# Power-Sheet-1.net
KiCad netlist of a schematic drawn in Altium Designer
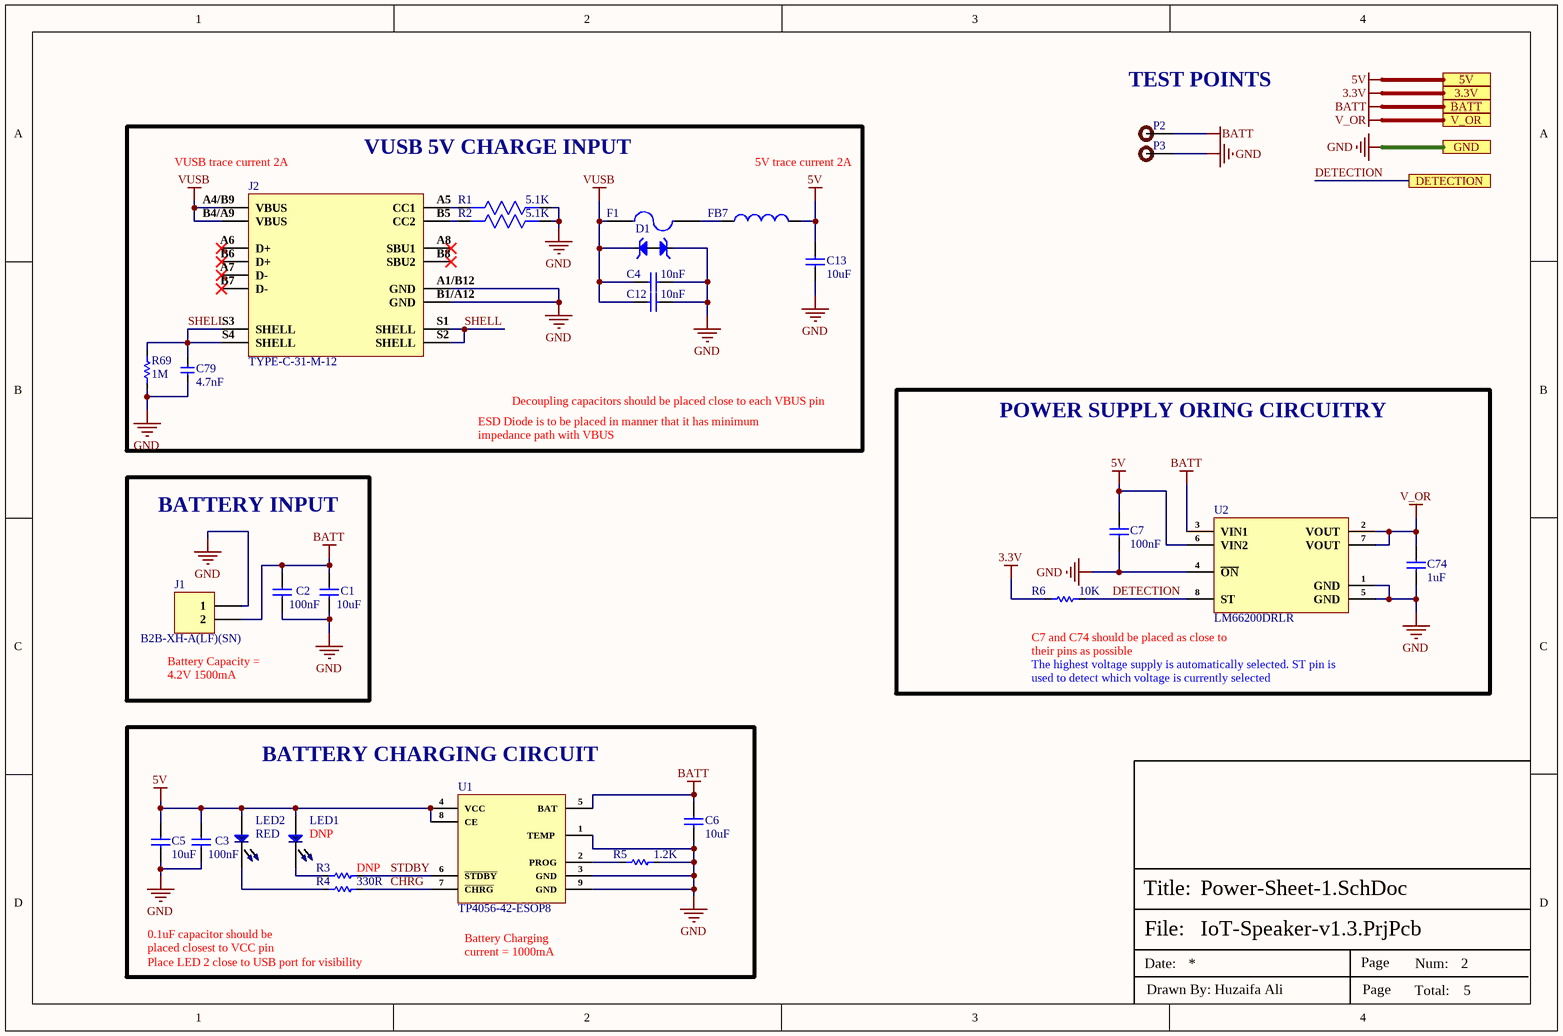
[diagram p0: Power-Sheet-1.SchDoc]

(export (version "E")
  (design (tool "Eeschema 10.0.6"))
  (components
    (comp (ref "C1")
      (value "10uF")
      (footprint "Cap-0805")
      (description "CAP CER 10UF 25V X5R 0805")
      (fields
        (field (name "MANUFACTURER") "Yageo")
        (field (name "MANUFACTURER PART NUMBER") "CC0805KKX5R8BB106")
      )
      (libsource (lib "eSpark_centralized_Library(2022)") (part "CC0805KKX5R8BB106"))
    )
    (comp (ref "C2")
      (value "100nF")
      (footprint "Cap-0402")
      (description "CAP CER 0.1UF 25V X5R 0402")
      (fields
        (field (name "MANUFACTURER") "Yageo")
        (field (name "MANUFACTURER PART NUMBER") "CC0402KRX5R8BB104")
      )
      (libsource (lib "eSpark_centralized_Library(2022)") (part "CC0402KRX5R8BB104"))
    )
    (comp (ref "C3")
      (value "100nF")
      (footprint "Cap-0402")
      (description "CAP CER 0.1UF 25V X5R 0402")
      (fields
        (field (name "MANUFACTURER") "Yageo")
        (field (name "MANUFACTURER PART NUMBER") "CC0402KRX5R8BB104")
      )
      (libsource (lib "eSpark_centralized_Library(2022)") (part "CC0402KRX5R8BB104"))
    )
    (comp (ref "C4")
      (value "10nF")
      (footprint "Cap-0603")
      (description "CAP CER 10000PF 50V C0G/NPO 0603")
      (fields
        (field (name "MANUFACTURER") "Yageo")
        (field (name "MANUFACTURER PART NUMBER") "CC0603JRNPO9BN103")
      )
      (libsource (lib "eSpark_centralized_Library(2022)") (part "CC0603JRNPO9BN103"))
    )
    (comp (ref "C5")
      (value "10uF")
      (footprint "Cap-0805")
      (description "CAP CER 10UF 25V X5R 0805")
      (fields
        (field (name "MANUFACTURER") "Yageo")
        (field (name "MANUFACTURER PART NUMBER") "CC0805KKX5R8BB106")
      )
      (libsource (lib "eSpark_centralized_Library(2022)") (part "CC0805KKX5R8BB106"))
    )
    (comp (ref "C6")
      (value "10uF")
      (footprint "Cap-0805")
      (description "CAP CER 10UF 25V X5R 0805")
      (fields
        (field (name "MANUFACTURER") "Yageo")
        (field (name "MANUFACTURER PART NUMBER") "CC0805KKX5R8BB106")
      )
      (libsource (lib "eSpark_centralized_Library(2022)") (part "CC0805KKX5R8BB106"))
    )
    (comp (ref "C7")
      (value "100nF")
      (footprint "Cap-0402")
      (description "CAP CER 0.1UF 25V X5R 0402")
      (fields
        (field (name "MANUFACTURER") "Yageo")
        (field (name "MANUFACTURER PART NUMBER") "CC0402KRX5R8BB104")
      )
      (libsource (lib "eSpark_centralized_Library(2022)") (part "CC0402KRX5R8BB104"))
    )
    (comp (ref "C12")
      (value "10nF")
      (footprint "Cap-0603")
      (description "CAP CER 10000PF 50V C0G/NPO 0603")
      (fields
        (field (name "MANUFACTURER") "Yageo")
        (field (name "MANUFACTURER PART NUMBER") "CC0603JRNPO9BN103")
      )
      (libsource (lib "eSpark_centralized_Library(2022)") (part "CC0603JRNPO9BN103"))
    )
    (comp (ref "C13")
      (value "10uF")
      (footprint "Cap-0805")
      (description "CAP CER 10UF 25V X5R 0805")
      (fields
        (field (name "MANUFACTURER") "Yageo")
        (field (name "MANUFACTURER PART NUMBER") "CC0805KKX5R8BB106")
      )
      (libsource (lib "eSpark_centralized_Library(2022)") (part "CC0805KKX5R8BB106"))
    )
    (comp (ref "C74")
      (value "1uF")
      (footprint "Cap-0603")
      (description "CAP CER 1UF 25V X5R 0603")
      (fields
        (field (name "MANUFACTURER") "Yageo")
        (field (name "MANUFACTURER PART NUMBER") "CC0603KRX5R8BB105")
      )
      (libsource (lib "eSpark_centralized_Library(2022)") (part "CC0603KRX5R8BB105"))
    )
    (comp (ref "C79")
      (value "4.7nF")
      (footprint "Cap-1206")
      (description "CAP CER 4700PF 1KV X7R 1206")
      (fields
        (field (name "MANUFACTURER") "Yageo")
        (field (name "MANUFACTURER PART NUMBER") "CC1206KKX7RCBB472")
      )
      (libsource (lib "eSpark Libraries") (part "CC1206KKX7RCBB472"))
    )
    (comp (ref "D1")
      (value "PESD5V0H1BSFYL")
      (footprint "DSN0603-2")
      (description "TVS DIODE 5VWM 6.3VC DSN0603-2")
      (fields (field (name "MANUFACTURER") "Nexperia") (field (name "LCSC PART NUMBER") "C477989"))
      (libsource (lib "eSpark Libraries") (part "PESD5V0H1BSFYL"))
    )
    (comp (ref "F1")
      (value "BSMD0805L-200")
      (footprint "Fuse-0805")
      (description "6V 2A 50A 1W -40℃~+85℃ 4A 4mΩ 5s 45mΩ 0805 Resettable Fuses ROHS")
      (fields (field (name "MANUFACTURER") "BHFUSE") (field (name "LCSC PART NUMBER") "C2757931"))
      (libsource (lib "eSpark_centralized_Library(2022)") (part "BSMD0805L-200"))
    )
    (comp (ref "FB7")
      (value "100MHz")
      (footprint "IND-1206")
      (description "FERRITE BEAD 120 OHM 1206 1LN")
      (fields
        (field (name "MANUFACTURER") "Murata")
        (field (name "MANUFACTURER PART NUMBER") "BLM31PG121SN1L")
      )
      (libsource (lib "eSpark_centralized_Library(2022)") (part "BLM31PG121SN1L"))
    )
    (comp (ref "J1")
      (value "B2B-XH-A(LF)(SN)")
      (footprint "B2B-XH-A(LF)(SN)_")
      (description "Conn Shrouded Header (4 Sides) HDR 2 POS 2.5mm Solder ST Thru-Hole Box")
      (fields (field (name "MANUFACTURER") "JST") (field (name "LCSC PART NUMBER") "C158012"))
      (libsource (lib "eSpark_centralized_Library(2022)") (part "B2B-XH-A(LF)(SN)"))
    )
    (comp (ref "J2")
      (value "TYPE-C-31-M-12")
      (footprint "TYPE-C-31-M-12_")
      (description "250mA 1 16 Female Type-C SMD USB Connectors ROHS")
      (fields
        (field (name "MANUFACTURER") "Korean Hroparts Elec")
        (field (name "LCSC PART NUMBER") "C165948")
      )
      (libsource (lib "eSpark_centralized_Library(2022)") (part "TYPE-C-31-M-12"))
    )
    (comp (ref "LED1")
      (value "DNP")
      (footprint "LED-0603")
      (description "Emerald 0603 Light Emitting Diodes (LED) ROHS")
      (fields
        (field (name "MANUFACTURER") "Foshan NationStar Optoelectronics")
        (field (name "MANUFACTURER PART NUMBER") "NCD0603G2")
      )
      (libsource (lib "eSpark_centralized_Library(2022)") (part "NCD0603G2"))
    )
    (comp (ref "LED2")
      (value "RED")
      (footprint "LED-0603")
      (description "0603 Light Emitting Diodes (LED) ROHS")
      (fields
        (field (name "MANUFACTURER") "Foshan NationStar Optoelectronics")
        (field (name "MANUFACTURER PART NUMBER") "NCD0603R3")
      )
      (libsource (lib "eSpark_centralized_Library(2022)") (part "NCD0603R3"))
    )
    (comp (ref "P2")
      (value "TEST POINT")
      (footprint "Test-point")
      (description "Test Point ON")
      (libsource (lib "eSpark_centralized_Library(2022)") (part "TEST POINT"))
    )
    (comp (ref "P3")
      (value "TEST POINT")
      (footprint "Test-point")
      (description "Test Point ON")
      (libsource (lib "eSpark_centralized_Library(2022)") (part "TEST POINT"))
    )
    (comp (ref "R1")
      (value "5.1K")
      (footprint "Res-0603")
      (description "RES 5.1K OHM 1% 1/10W 0603")
      (fields
        (field (name "MANUFACTURER") "Yageo")
        (field (name "MANUFACTURER PART NUMBER") "RC0603FR-075K1L")
      )
      (libsource (lib "eSpark_centralized_Library(2022)") (part "RC0603FR-075K1L"))
    )
    (comp (ref "R2")
      (value "5.1K")
      (footprint "Res-0603")
      (description "RES 5.1K OHM 1% 1/10W 0603")
      (fields
        (field (name "MANUFACTURER") "Yageo")
        (field (name "MANUFACTURER PART NUMBER") "RC0603FR-075K1L")
      )
      (libsource (lib "eSpark_centralized_Library(2022)") (part "RC0603FR-075K1L"))
    )
    (comp (ref "R3")
      (value "DNP")
      (footprint "Res-0603")
      (description "RES SMD 220 OHM 1% 1/10W 0603")
      (fields
        (field (name "MANUFACTURER") "Yageo")
        (field (name "MANUFACTURER PART NUMBER") "RC0603FR-07220RL")
      )
      (libsource (lib "eSpark_centralized_Library(2022)") (part "RC0603FR-07220RL"))
    )
    (comp (ref "R4")
      (value "330R")
      (footprint "Res-0603")
      (description "RES  SMD 330R 100 mW 0603")
      (fields
        (field (name "MANUFACTURER") "Yageo")
        (field (name "MANUFACTURER PART NUMBER") "RC0603JR-07330RL")
      )
      (libsource (lib "eSpark_centralized_Library(2022)") (part "RC0603JR-07330RL"))
    )
    (comp (ref "R5")
      (value "1.2K")
      (footprint "Res-0603")
      (description "Thick Film Resistors 75V 1.2kΩ 0603 Chip Resistor - Surface Mount ROHS")
      (fields
        (field (name "MANUFACTURER") "UNI-ROYAL")
        (field (name "MANUFACTURER PART NUMBER") "0603WAF1201T5E")
      )
      (libsource (lib "eSpark_centralized_Library(2022)") (part "0603WAF1201T5E"))
    )
    (comp (ref "R6")
      (value "10K")
      (footprint "Res-0603")
      (description "RES SMD 10K Ohm 1% 1/10W 0603")
      (fields
        (field (name "MANUFACTURER") "Yageo")
        (field (name "MANUFACTURER PART NUMBER") "RC0603FR-0710KL")
      )
      (libsource (lib "eSpark_centralized_Library(2022)") (part "RC0603FR-0710KL"))
    )
    (comp (ref "R69")
      (value "1M")
      (footprint "Res-0603")
      (description "RES SMD 1M OHM 1% 1/10W 0603")
      (fields
        (field (name "MANUFACTURER") "Yageo")
        (field (name "MANUFACTURER PART NUMBER") "RC0603FR-071ML")
      )
      (libsource (lib "eSpark Libraries") (part "RC0603FR-071ML"))
    )
    (comp (ref "U1")
      (value "TP4056-42-ESOP8")
      (footprint "ESOP-8")
      (description "ESOP-8 Battery Management ICs ROHS")
      (fields (field (name "MANUFACTURER") "TOPPOWER") (field (name "LCSC PART NUMBER") "C16581"))
      (libsource (lib "eSpark_centralized_Library(2022)") (part "TP4056-42-ESOP8"))
    )
    (comp (ref "U2")
      (value "LM66200DRLR")
      (footprint "SOT-583")
      (description "OR Controller N+1 ORing Controller N-Channel 2:1 SOT-583")
      (fields (field (name "MANUFACTURER") "Texas Instruments") (field (name "LCSC PART NUMBER") "C3235556"))
      (libsource (lib "eSpark_centralized_Library(2022)") (part "LM66200DRLR"))
    )
  )
  (nets
    (net (code "1") (name "/CHRG") (class "Default")
      (node (ref "R4") (pin "2") (pinfunction "2_2") (pintype "passive"))
      (node (ref "U1") (pin "7") (pinfunction "~{CHRG}_7") (pintype "passive"))
    )
    (net (code "2") (name "/DETECTION") (class "Default")
      (node (ref "R6") (pin "2") (pinfunction "2_2") (pintype "passive"))
      (node (ref "U2") (pin "8") (pinfunction "ST_8") (pintype "passive"))
    )
    (net (code "3") (name "/SHELL") (class "Default")
      (node (ref "C79") (pin "2") (pinfunction "2_2") (pintype "passive"))
      (node (ref "J2") (pin "S1") (pinfunction "SHELL_S1") (pintype "passive"))
      (node (ref "J2") (pin "S2") (pinfunction "SHELL_S2") (pintype "passive"))
      (node (ref "J2") (pin "S3") (pinfunction "SHELL_S3") (pintype "passive"))
      (node (ref "J2") (pin "S4") (pinfunction "SHELL_S4") (pintype "passive"))
      (node (ref "R69") (pin "2") (pinfunction "2_2") (pintype "passive"))
    )
    (net (code "4") (name "/STDBY") (class "Default")
      (node (ref "R3") (pin "2") (pinfunction "2_2") (pintype "passive"))
      (node (ref "U1") (pin "6") (pinfunction "~{STDBY}_6") (pintype "passive"))
    )
    (net (code "5") (name "3.3V") (class "Default")
      (node (ref "R6") (pin "1") (pinfunction "1_1") (pintype "passive"))
    )
    (net (code "6") (name "5V") (class "Default")
      (node (ref "C13") (pin "2") (pinfunction "2_2") (pintype "passive"))
      (node (ref "C3") (pin "2") (pinfunction "2_2") (pintype "passive"))
      (node (ref "C5") (pin "2") (pinfunction "2_2") (pintype "passive"))
      (node (ref "C7") (pin "2") (pinfunction "2_2") (pintype "passive"))
      (node (ref "FB7") (pin "2") (pinfunction "2_2") (pintype "passive"))
      (node (ref "LED1") (pin "1") (pinfunction "1_1") (pintype "passive"))
      (node (ref "LED2") (pin "1") (pinfunction "1_1") (pintype "passive"))
      (node (ref "U1") (pin "4") (pinfunction "VCC_4") (pintype "passive"))
      (node (ref "U1") (pin "8") (pinfunction "CE_8") (pintype "passive"))
      (node (ref "U2") (pin "6") (pinfunction "VIN2_6") (pintype "passive"))
    )
    (net (code "7") (name "BATT") (class "Default")
      (node (ref "C1") (pin "2") (pinfunction "2_2") (pintype "passive"))
      (node (ref "C2") (pin "2") (pinfunction "2_2") (pintype "passive"))
      (node (ref "C6") (pin "2") (pinfunction "2_2") (pintype "passive"))
      (node (ref "J1") (pin "2") (pinfunction "2_2") (pintype "passive"))
      (node (ref "P2") (pin "1") (pinfunction "1_1") (pintype "passive"))
      (node (ref "U1") (pin "5") (pinfunction "BAT_5") (pintype "passive"))
      (node (ref "U2") (pin "3") (pinfunction "VIN1_3") (pintype "passive"))
    )
    (net (code "8") (name "GND") (class "Default")
      (node (ref "C1") (pin "1") (pinfunction "1_1") (pintype "passive"))
      (node (ref "C12") (pin "2") (pinfunction "2_2") (pintype "passive"))
      (node (ref "C13") (pin "1") (pinfunction "1_1") (pintype "passive"))
      (node (ref "C2") (pin "1") (pinfunction "1_1") (pintype "passive"))
      (node (ref "C3") (pin "1") (pinfunction "1_1") (pintype "passive"))
      (node (ref "C4") (pin "2") (pinfunction "2_2") (pintype "passive"))
      (node (ref "C5") (pin "1") (pinfunction "1_1") (pintype "passive"))
      (node (ref "C6") (pin "1") (pinfunction "1_1") (pintype "passive"))
      (node (ref "C7") (pin "1") (pinfunction "1_1") (pintype "passive"))
      (node (ref "C74") (pin "1") (pinfunction "1_1") (pintype "passive"))
      (node (ref "C79") (pin "1") (pinfunction "1_1") (pintype "passive"))
      (node (ref "D1") (pin "2") (pinfunction "2_2") (pintype "passive"))
      (node (ref "J1") (pin "1") (pinfunction "1_1") (pintype "passive"))
      (node (ref "J2") (pin "A1/B12") (pinfunction "GND_A1/B12") (pintype "power_in"))
      (node (ref "J2") (pin "B1/A12") (pinfunction "GND_B1/A12") (pintype "power_in"))
      (node (ref "P3") (pin "1") (pinfunction "1_1") (pintype "passive"))
      (node (ref "R1") (pin "1") (pintype "passive"))
      (node (ref "R2") (pin "1") (pintype "passive"))
      (node (ref "R5") (pin "1") (pinfunction "1_1") (pintype "passive"))
      (node (ref "R69") (pin "1") (pinfunction "1_1") (pintype "passive"))
      (node (ref "U1") (pin "1") (pinfunction "TEMP_1") (pintype "passive"))
      (node (ref "U1") (pin "3") (pinfunction "GND_3") (pintype "passive"))
      (node (ref "U1") (pin "9") (pinfunction "GND_9") (pintype "passive"))
      (node (ref "U2") (pin "1") (pinfunction "GND_1") (pintype "passive"))
      (node (ref "U2") (pin "4") (pinfunction "~{ON}_4") (pintype "passive"))
      (node (ref "U2") (pin "5") (pinfunction "GND_5") (pintype "passive"))
    )
    (net (code "9") (name "Net-(F1-Pad2)") (class "Default")
      (node (ref "F1") (pin "2") (pinfunction "2_2") (pintype "passive"))
      (node (ref "FB7") (pin "1") (pinfunction "1_1") (pintype "passive"))
    )
    (net (code "10") (name "Net-(J2-CC1)") (class "Default")
      (node (ref "J2") (pin "A5") (pinfunction "CC1_A5") (pintype "passive"))
      (node (ref "R1") (pin "2") (pintype "passive"))
    )
    (net (code "11") (name "Net-(J2-CC2)") (class "Default")
      (node (ref "J2") (pin "B5") (pinfunction "CC2_B5") (pintype "passive"))
      (node (ref "R2") (pin "2") (pintype "passive"))
    )
    (net (code "12") (name "Net-(LED1-Pad2)") (class "Default")
      (node (ref "LED1") (pin "2") (pinfunction "2_2") (pintype "passive"))
      (node (ref "R3") (pin "1") (pinfunction "1_1") (pintype "passive"))
    )
    (net (code "13") (name "Net-(LED2-Pad2)") (class "Default")
      (node (ref "LED2") (pin "2") (pinfunction "2_2") (pintype "passive"))
      (node (ref "R4") (pin "1") (pinfunction "1_1") (pintype "passive"))
    )
    (net (code "14") (name "Net-(U1-PROG)") (class "Default")
      (node (ref "R5") (pin "2") (pinfunction "2_2") (pintype "passive"))
      (node (ref "U1") (pin "2") (pinfunction "PROG_2") (pintype "passive"))
    )
    (net (code "15") (name "VUSB") (class "Default")
      (node (ref "C12") (pin "1") (pinfunction "1_1") (pintype "passive"))
      (node (ref "C4") (pin "1") (pinfunction "1_1") (pintype "passive"))
      (node (ref "D1") (pin "1") (pinfunction "1_1") (pintype "passive"))
      (node (ref "F1") (pin "1") (pinfunction "1_1") (pintype "passive"))
      (node (ref "J2") (pin "A4/B9") (pinfunction "VBUS_A4/B9") (pintype "power_in"))
      (node (ref "J2") (pin "B4/A9") (pinfunction "VBUS_B4/A9") (pintype "power_in"))
    )
    (net (code "16") (name "V_OR") (class "Default")
      (node (ref "C74") (pin "2") (pinfunction "2_2") (pintype "passive"))
      (node (ref "U2") (pin "2") (pinfunction "VOUT_2") (pintype "passive"))
      (node (ref "U2") (pin "7") (pinfunction "VOUT_7") (pintype "passive"))
    )
    (net (code "17") (name "unconnected-(J2-D+-PadA6)") (class "Default")
      (node (ref "J2") (pin "A6") (pinfunction "D+_A6") (pintype "passive+no_connect"))
    )
    (net (code "18") (name "unconnected-(J2-D+-PadB6)") (class "Default")
      (node (ref "J2") (pin "B6") (pinfunction "D+_B6") (pintype "passive+no_connect"))
    )
    (net (code "19") (name "unconnected-(J2-D--PadA7)") (class "Default")
      (node (ref "J2") (pin "A7") (pinfunction "D-_A7") (pintype "passive+no_connect"))
    )
    (net (code "20") (name "unconnected-(J2-D--PadB7)") (class "Default")
      (node (ref "J2") (pin "B7") (pinfunction "D-_B7") (pintype "passive+no_connect"))
    )
    (net (code "21") (name "unconnected-(J2-SBU1-PadA8)") (class "Default")
      (node (ref "J2") (pin "A8") (pinfunction "SBU1_A8") (pintype "passive+no_connect"))
    )
    (net (code "22") (name "unconnected-(J2-SBU2-PadB8)") (class "Default")
      (node (ref "J2") (pin "B8") (pinfunction "SBU2_B8") (pintype "passive+no_connect"))
    )
  )
)
